# 240_current_measurement.net
KiCad netlist of a schematic drawn in EAGLE
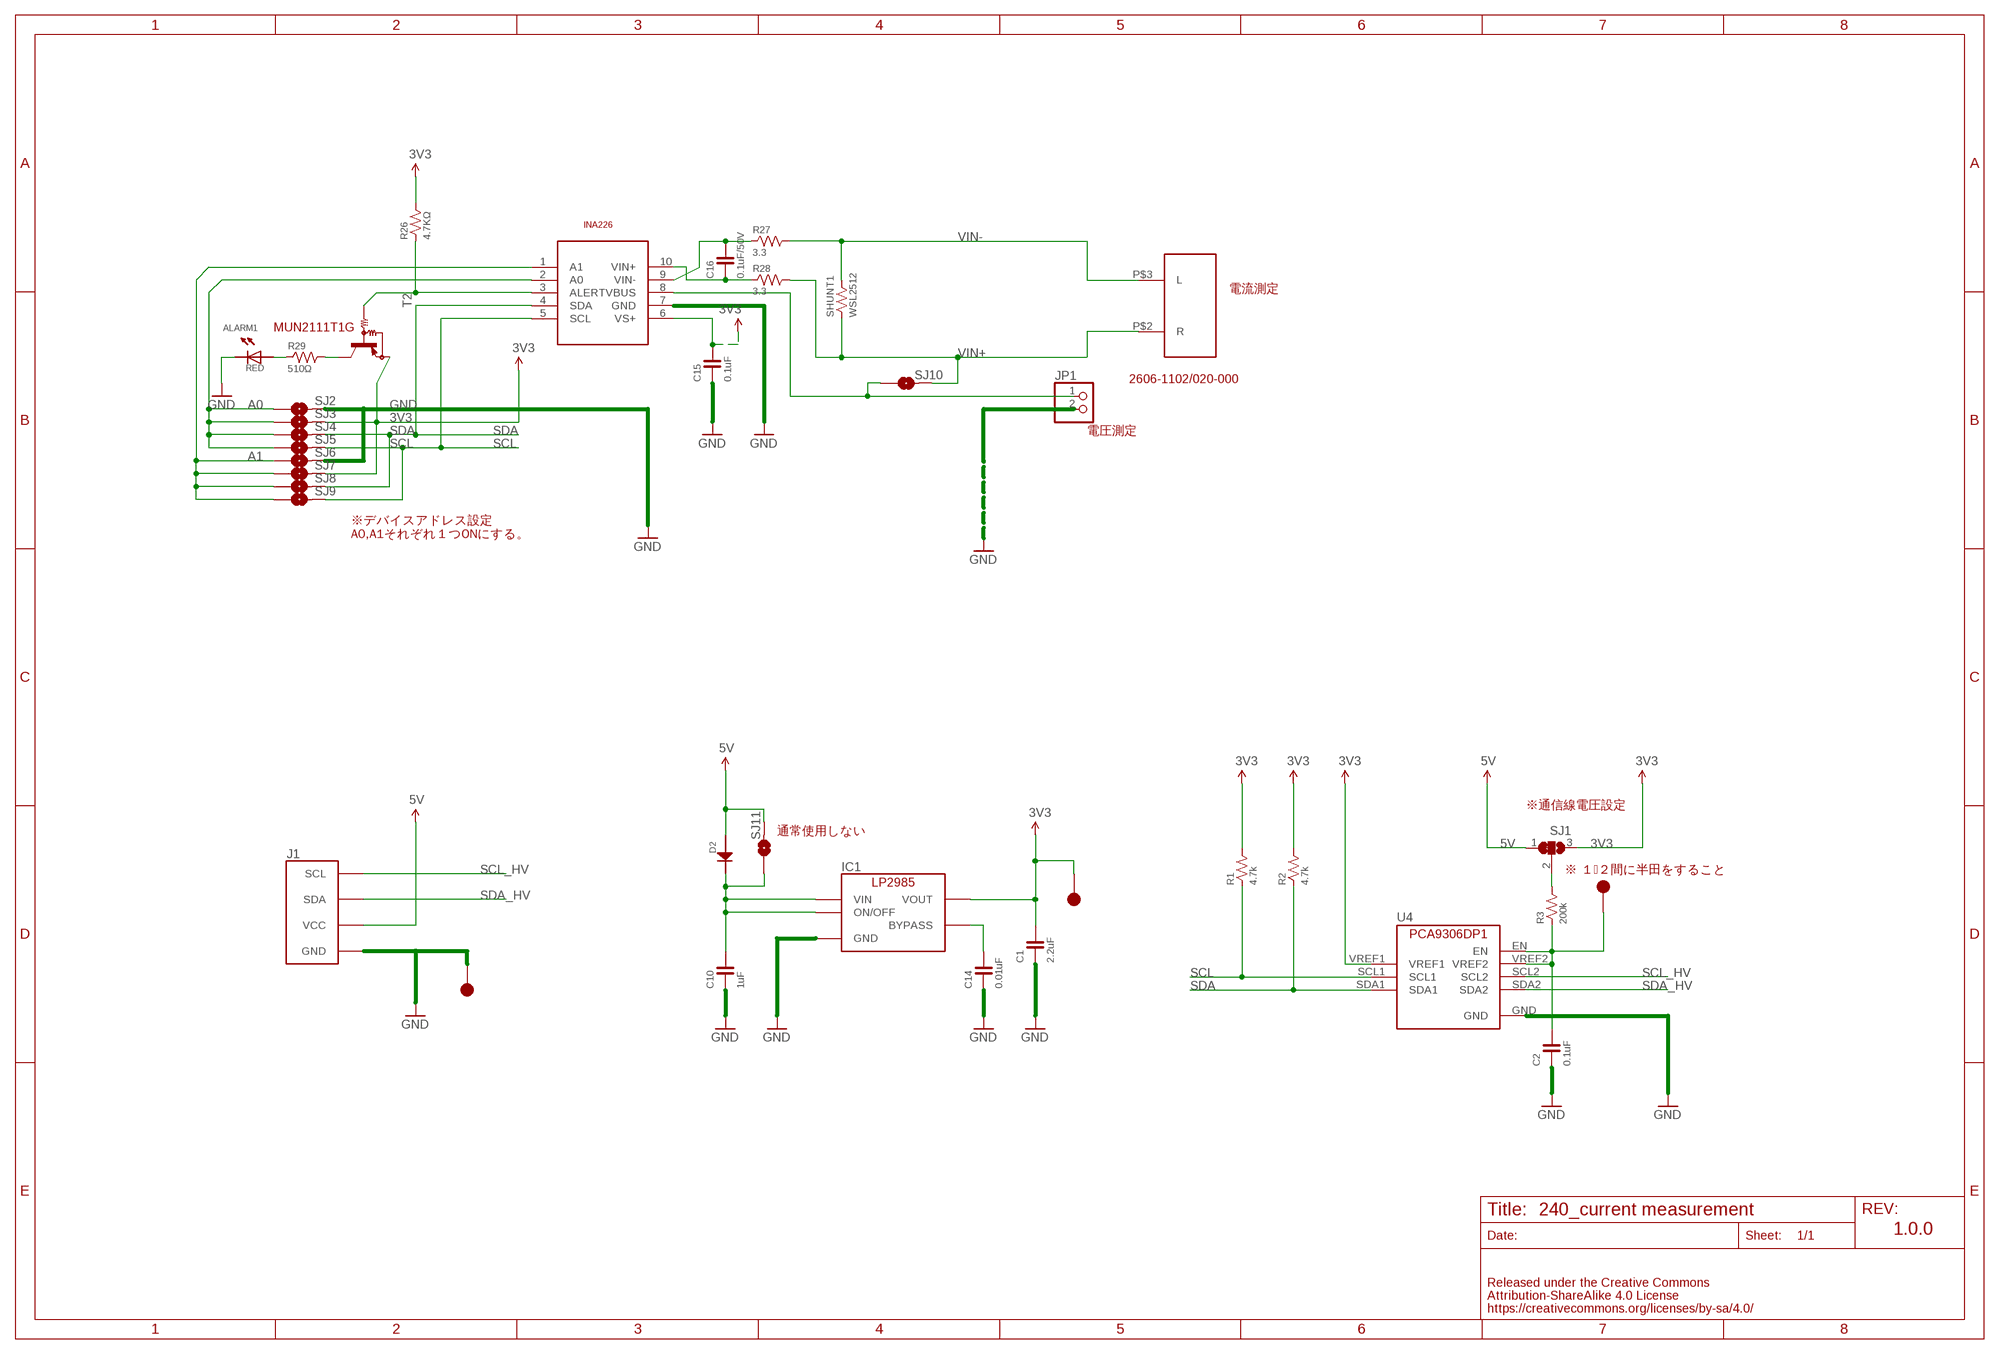
[diagram p0: schematic, sheet 1]

(export (version "E")
  (design (tool "Eeschema 10.0.6"))
  (components
    (comp (ref "ALARM1")
      (value "RED")
      (footprint "eagle-import:0603")
      (libsource (lib "eagle-import") (part "LED-0603"))
    )
    (comp (ref "C1")
      (value "2.2uF")
      (footprint "eagle-import:0603")
      (libsource (lib "eagle-import") (part "CAPACITOR-0603"))
    )
    (comp (ref "C2")
      (value "0.1uF")
      (footprint "eagle-import:0603")
      (libsource (lib "eagle-import") (part "CAPACITOR-0603"))
    )
    (comp (ref "C10")
      (value "1uF")
      (footprint "eagle-import:0603")
      (libsource (lib "eagle-import") (part "CAPACITOR-0603"))
    )
    (comp (ref "C14")
      (value "0.01uF")
      (footprint "eagle-import:0603")
      (libsource (lib "eagle-import") (part "CAPACITOR-0603"))
    )
    (comp (ref "C15")
      (value "0.1uF")
      (footprint "eagle-import:0603")
      (libsource (lib "eagle-import") (part "CAPACITOR-0603"))
    )
    (comp (ref "C16")
      (value "0.1uF/50V")
      (footprint "eagle-import:0603")
      (libsource (lib "eagle-import") (part "CAPACITOR-0603"))
    )
    (comp (ref "D2")
      (value "1N4148")
      (footprint "eagle-import:1N4148W")
      (libsource (lib "eagle-import") (part "1N4148"))
    )
    (comp (ref "IC1")
      (value "LP2985-33")
      (footprint "eagle-import:SOT-23-5")
      (libsource (lib "eagle-import") (part "LP2985-33DBV"))
    )
    (comp (ref "J1")
      (value "FABO_BRICK_I2C-S04B-PASK-2")
      (footprint "eagle-import:FABO_BRICK_I2C_S04B-PASK-2")
      (libsource (lib "eagle-import") (part "FABO_BRICK_I2C-S04B-PASK-2"))
    )
    (comp (ref "JP1")
      (value "PINHD-1X2")
      (footprint "eagle-import:1X02")
      (libsource (lib "eagle-import") (part "PINHD-1X2"))
    )
    (comp (ref "R1")
      (value "4.7k")
      (footprint "eagle-import:0603")
      (libsource (lib "eagle-import") (part "RESISTOR-0603"))
    )
    (comp (ref "R2")
      (value "4.7k")
      (footprint "eagle-import:0603")
      (libsource (lib "eagle-import") (part "RESISTOR-0603"))
    )
    (comp (ref "R3")
      (value "200k")
      (footprint "eagle-import:0603")
      (libsource (lib "eagle-import") (part "RESISTOR-0603"))
    )
    (comp (ref "R26")
      (value "4.7KΩ")
      (footprint "eagle-import:0603")
      (libsource (lib "eagle-import") (part "RESISTOR-0603"))
    )
    (comp (ref "R27")
      (value "3.3")
      (footprint "eagle-import:0603")
      (libsource (lib "eagle-import") (part "RESISTOR-0603"))
    )
    (comp (ref "R28")
      (value "3.3")
      (footprint "eagle-import:0603")
      (libsource (lib "eagle-import") (part "RESISTOR-0603"))
    )
    (comp (ref "R29")
      (value "510Ω")
      (footprint "eagle-import:0603")
      (libsource (lib "eagle-import") (part "RESISTOR-0603"))
    )
    (comp (ref "SHUNT1")
      (value "WSL2512")
      (footprint "eagle-import:2512INCH")
      (libsource (lib "eagle-import") (part "WSL2512"))
    )
    (comp (ref "SJ1")
      (value "SJ2W")
      (footprint "eagle-import:SJ_2")
      (libsource (lib "eagle-import") (part "SJ2W"))
    )
    (comp (ref "SJ2")
      (value "FABO-SMD-JUMPER-SELECT")
      (footprint "eagle-import:SMD-JUMPER_SELECT")
      (libsource (lib "eagle-import") (part "FABO-SMD-JUMPER-SELECT"))
    )
    (comp (ref "SJ3")
      (value "FABO-SMD-JUMPER-SELECT")
      (footprint "eagle-import:SMD-JUMPER_SELECT")
      (libsource (lib "eagle-import") (part "FABO-SMD-JUMPER-SELECT"))
    )
    (comp (ref "SJ4")
      (value "FABO-SMD-JUMPER-SELECT")
      (footprint "eagle-import:SMD-JUMPER_SELECT")
      (libsource (lib "eagle-import") (part "FABO-SMD-JUMPER-SELECT"))
    )
    (comp (ref "SJ5")
      (value "FABO-SMD-JUMPER-SELECT")
      (footprint "eagle-import:SMD-JUMPER_SELECT")
      (libsource (lib "eagle-import") (part "FABO-SMD-JUMPER-SELECT"))
    )
    (comp (ref "SJ6")
      (value "FABO-SMD-JUMPER-SELECT")
      (footprint "eagle-import:SMD-JUMPER_SELECT")
      (libsource (lib "eagle-import") (part "FABO-SMD-JUMPER-SELECT"))
    )
    (comp (ref "SJ7")
      (value "FABO-SMD-JUMPER-SELECT")
      (footprint "eagle-import:SMD-JUMPER_SELECT")
      (libsource (lib "eagle-import") (part "FABO-SMD-JUMPER-SELECT"))
    )
    (comp (ref "SJ8")
      (value "FABO-SMD-JUMPER-SELECT")
      (footprint "eagle-import:SMD-JUMPER_SELECT")
      (libsource (lib "eagle-import") (part "FABO-SMD-JUMPER-SELECT"))
    )
    (comp (ref "SJ9")
      (value "FABO-SMD-JUMPER-SELECT")
      (footprint "eagle-import:SMD-JUMPER_SELECT")
      (libsource (lib "eagle-import") (part "FABO-SMD-JUMPER-SELECT"))
    )
    (comp (ref "SJ10")
      (value "FABO-SMD-JUMPER-SELECT")
      (footprint "eagle-import:SMD-JUMPER_SELECT")
      (libsource (lib "eagle-import") (part "FABO-SMD-JUMPER-SELECT"))
    )
    (comp (ref "SJ11")
      (value "FABO-SMD-JUMPER-SELECT")
      (footprint "eagle-import:SMD-JUMPER_SELECT")
      (libsource (lib "eagle-import") (part "FABO-SMD-JUMPER-SELECT"))
    )
    (comp (ref "T2")
      (value "MUN2111T1-PNP_DRIVER-SC59-BEC")
      (footprint "eagle-import:SC59-BEC")
      (libsource (lib "eagle-import") (part "-PNP_DRIVER-SC59-BECMUN2111T1"))
    )
    (comp (ref "TP1")
      (value "TP-15")
      (footprint "eagle-import:TP-15")
      (libsource (lib "eagle-import") (part "TP-15"))
    )
    (comp (ref "TP2")
      (value "TP-15")
      (footprint "eagle-import:TP-15")
      (libsource (lib "eagle-import") (part "TP-15"))
    )
    (comp (ref "TP5")
      (value "TP-15")
      (footprint "eagle-import:TP-15")
      (libsource (lib "eagle-import") (part "TP-15"))
    )
    (comp (ref "U$1")
      (value "2606-1102_2")
      (footprint "eagle-import:2606-1102_020-000")
      (libsource (lib "eagle-import") (part "2606-1102_2"))
    )
    (comp (ref "U3")
      (value "TI-INA226")
      (footprint "eagle-import:TI-INA226")
      (libsource (lib "eagle-import") (part "TI-INA226"))
    )
    (comp (ref "U4")
      (value "PCA9306DP1")
      (footprint "eagle-import:TSSOP8")
      (libsource (lib "eagle-import") (part "PCA9306DP1"))
    )
  )
  (nets
    (net (code "1") (name "/A0") (class "Default")
      (node (ref "SJ2") (pin "1") (pinfunction "1_1") (pintype "passive"))
      (node (ref "SJ3") (pin "1") (pinfunction "1_1") (pintype "passive"))
      (node (ref "SJ4") (pin "1") (pinfunction "1_1") (pintype "passive"))
      (node (ref "SJ5") (pin "1") (pinfunction "1_1") (pintype "passive"))
      (node (ref "U3") (pin "2") (pinfunction "A0_2") (pintype "bidirectional"))
    )
    (net (code "2") (name "/A1") (class "Default")
      (node (ref "SJ6") (pin "1") (pinfunction "1_1") (pintype "passive"))
      (node (ref "SJ7") (pin "1") (pinfunction "1_1") (pintype "passive"))
      (node (ref "SJ8") (pin "1") (pinfunction "1_1") (pintype "passive"))
      (node (ref "SJ9") (pin "1") (pinfunction "1_1") (pintype "passive"))
      (node (ref "U3") (pin "1") (pinfunction "A1_1") (pintype "bidirectional"))
    )
    (net (code "3") (name "/SCL") (class "Default")
      (node (ref "R1") (pin "1") (pinfunction "1_1") (pintype "bidirectional"))
      (node (ref "SJ5") (pin "2") (pinfunction "2_2") (pintype "passive"))
      (node (ref "SJ9") (pin "2") (pinfunction "2_2") (pintype "passive"))
      (node (ref "U3") (pin "5") (pinfunction "SCL_5") (pintype "bidirectional"))
      (node (ref "U4") (pin "SCL1") (pinfunction "SCL1_SCL1") (pintype "bidirectional"))
    )
    (net (code "4") (name "/SCL_HV") (class "Default")
      (node (ref "J1") (pin "SCL") (pinfunction "SCL_SCL") (pintype "bidirectional"))
      (node (ref "U4") (pin "SCL2") (pinfunction "SCL2_SCL2") (pintype "bidirectional"))
    )
    (net (code "5") (name "/SDA") (class "Default")
      (node (ref "R2") (pin "1") (pinfunction "1_1") (pintype "bidirectional"))
      (node (ref "SJ4") (pin "2") (pinfunction "2_2") (pintype "passive"))
      (node (ref "SJ8") (pin "2") (pinfunction "2_2") (pintype "passive"))
      (node (ref "U3") (pin "4") (pinfunction "SDA_4") (pintype "bidirectional"))
      (node (ref "U4") (pin "SDA1") (pinfunction "SDA1_SDA1") (pintype "bidirectional"))
    )
    (net (code "6") (name "/SDA_HV") (class "Default")
      (node (ref "J1") (pin "SDA") (pinfunction "SDA_SDA") (pintype "bidirectional"))
      (node (ref "U4") (pin "SDA2") (pinfunction "SDA2_SDA2") (pintype "bidirectional"))
    )
    (net (code "7") (name "/VIN+") (class "Default")
      (node (ref "R28") (pin "2") (pinfunction "2_2") (pintype "bidirectional"))
      (node (ref "SHUNT1") (pin "P$1") (pinfunction "1_P$1") (pintype "bidirectional"))
      (node (ref "SJ10") (pin "2") (pinfunction "2_2") (pintype "passive"))
      (node (ref "U$1") (pin "P$2") (pinfunction "R_P$2") (pintype "bidirectional"))
    )
    (net (code "8") (name "/VIN-") (class "Default")
      (node (ref "R27") (pin "2") (pinfunction "2_2") (pintype "bidirectional"))
      (node (ref "SHUNT1") (pin "P$2") (pinfunction "2_P$2") (pintype "bidirectional"))
      (node (ref "U$1") (pin "P$3") (pinfunction "L_P$3") (pintype "bidirectional"))
    )
    (net (code "9") (name "3V3") (class "Default")
      (node (ref "C1") (pin "2") (pinfunction "2_2") (pintype "passive"))
      (node (ref "C15") (pin "2") (pinfunction "2_2") (pintype "passive"))
      (node (ref "IC1") (pin "5") (pinfunction "VOUT_5") (pintype "output"))
      (node (ref "R1") (pin "2") (pinfunction "2_2") (pintype "bidirectional"))
      (node (ref "R2") (pin "2") (pinfunction "2_2") (pintype "bidirectional"))
      (node (ref "R26") (pin "2") (pinfunction "2_2") (pintype "bidirectional"))
      (node (ref "SJ1") (pin "3") (pinfunction "3_3") (pintype "passive"))
      (node (ref "SJ3") (pin "2") (pinfunction "2_2") (pintype "passive"))
      (node (ref "SJ7") (pin "2") (pinfunction "2_2") (pintype "passive"))
      (node (ref "T2") (pin "E") (pinfunction "E_E") (pintype "passive"))
      (node (ref "TP5") (pin "1") (pinfunction "1_1") (pintype "bidirectional"))
      (node (ref "U3") (pin "6") (pinfunction "VS+_6") (pintype "bidirectional"))
      (node (ref "U4") (pin "VREF1") (pinfunction "VREF1_VREF1") (pintype "bidirectional"))
    )
    (net (code "10") (name "5V") (class "Default")
      (node (ref "D2") (pin "ANODE") (pinfunction "ANODE_ANODE") (pintype "bidirectional"))
      (node (ref "J1") (pin "VCC") (pinfunction "VCC_VCC") (pintype "bidirectional"))
      (node (ref "SJ1") (pin "1") (pinfunction "1_1") (pintype "passive"))
      (node (ref "SJ11") (pin "2") (pinfunction "2_2") (pintype "passive"))
    )
    (net (code "11") (name "GND") (class "Default")
      (node (ref "ALARM1") (pin "CATHODE") (pinfunction "CATHODE_CATHODE") (pintype "passive"))
      (node (ref "C1") (pin "1") (pinfunction "1_1") (pintype "passive"))
      (node (ref "C10") (pin "1") (pinfunction "1_1") (pintype "passive"))
      (node (ref "C14") (pin "1") (pinfunction "1_1") (pintype "passive"))
      (node (ref "C15") (pin "1") (pinfunction "1_1") (pintype "passive"))
      (node (ref "C2") (pin "1") (pinfunction "1_1") (pintype "passive"))
      (node (ref "IC1") (pin "2") (pinfunction "GND_2") (pintype "power_in"))
      (node (ref "J1") (pin "GND") (pinfunction "GND_GND") (pintype "bidirectional"))
      (node (ref "JP1") (pin "2") (pinfunction "2_2") (pintype "passive"))
      (node (ref "SJ2") (pin "2") (pinfunction "2_2") (pintype "passive"))
      (node (ref "SJ6") (pin "2") (pinfunction "2_2") (pintype "passive"))
      (node (ref "TP1") (pin "1") (pinfunction "1_1") (pintype "bidirectional"))
      (node (ref "U3") (pin "7") (pinfunction "GND_7") (pintype "bidirectional"))
      (node (ref "U4") (pin "GND") (pinfunction "GND_GND") (pintype "bidirectional"))
    )
    (net (code "12") (name "Net-(ALARM1-PadANODE)") (class "Default")
      (node (ref "ALARM1") (pin "ANODE") (pinfunction "ANODE_ANODE") (pintype "passive"))
      (node (ref "R29") (pin "1") (pinfunction "1_1") (pintype "bidirectional"))
    )
    (net (code "13") (name "Net-(C2-Pad2)") (class "Default")
      (node (ref "C2") (pin "2") (pinfunction "2_2") (pintype "passive"))
      (node (ref "R3") (pin "1") (pinfunction "1_1") (pintype "bidirectional"))
      (node (ref "TP2") (pin "1") (pinfunction "1_1") (pintype "bidirectional"))
      (node (ref "U4") (pin "EN") (pinfunction "EN_EN") (pintype "bidirectional"))
      (node (ref "U4") (pin "VREF2") (pinfunction "VREF2_VREF2") (pintype "bidirectional"))
    )
    (net (code "14") (name "Net-(IC1-BYPASS)") (class "Default")
      (node (ref "C14") (pin "2") (pinfunction "2_2") (pintype "passive"))
      (node (ref "IC1") (pin "4") (pinfunction "BYPASS_4") (pintype "bidirectional"))
    )
    (net (code "15") (name "Net-(IC1-ON{slash}OFF)") (class "Default")
      (node (ref "C10") (pin "2") (pinfunction "2_2") (pintype "passive"))
      (node (ref "D2") (pin "CATHODE") (pinfunction "CATHODE_CATHODE") (pintype "bidirectional"))
      (node (ref "IC1") (pin "1") (pinfunction "VIN_1") (pintype "input"))
      (node (ref "IC1") (pin "3") (pinfunction "ON/OFF_3") (pintype "input"))
      (node (ref "SJ11") (pin "1") (pinfunction "1_1") (pintype "passive"))
    )
    (net (code "16") (name "Net-(R3-Pad2)") (class "Default")
      (node (ref "R3") (pin "2") (pinfunction "2_2") (pintype "bidirectional"))
      (node (ref "SJ1") (pin "2") (pinfunction "2_2") (pintype "passive"))
    )
    (net (code "17") (name "Net-(R29-Pad2)") (class "Default")
      (node (ref "R29") (pin "2") (pinfunction "2_2") (pintype "bidirectional"))
      (node (ref "T2") (pin "C") (pinfunction "C_C") (pintype "passive"))
    )
    (net (code "18") (name "Net-(U3-ALERT)") (class "Default")
      (node (ref "R26") (pin "1") (pinfunction "1_1") (pintype "bidirectional"))
      (node (ref "T2") (pin "B") (pinfunction "B_B") (pintype "passive"))
      (node (ref "U3") (pin "3") (pinfunction "ALERT_3") (pintype "bidirectional"))
    )
    (net (code "19") (name "Net-(U3-VBUS)") (class "Default")
      (node (ref "JP1") (pin "1") (pinfunction "1_1") (pintype "passive"))
      (node (ref "SJ10") (pin "1") (pinfunction "1_1") (pintype "passive"))
      (node (ref "U3") (pin "8") (pinfunction "VBUS_8") (pintype "bidirectional"))
    )
    (net (code "20") (name "Net-(U3-VIN+)") (class "Default")
      (node (ref "C16") (pin "1") (pinfunction "1_1") (pintype "passive"))
      (node (ref "R28") (pin "1") (pinfunction "1_1") (pintype "bidirectional"))
      (node (ref "U3") (pin "10") (pinfunction "VIN+_10") (pintype "bidirectional"))
    )
    (net (code "21") (name "Net-(U3-VIN-)") (class "Default")
      (node (ref "C16") (pin "2") (pinfunction "2_2") (pintype "passive"))
      (node (ref "R27") (pin "1") (pinfunction "1_1") (pintype "bidirectional"))
      (node (ref "U3") (pin "9") (pinfunction "VIN-_9") (pintype "bidirectional"))
    )
  )
)
